# FC_MC_SCH.net
KiCad netlist of a schematic drawn in Altium Designer
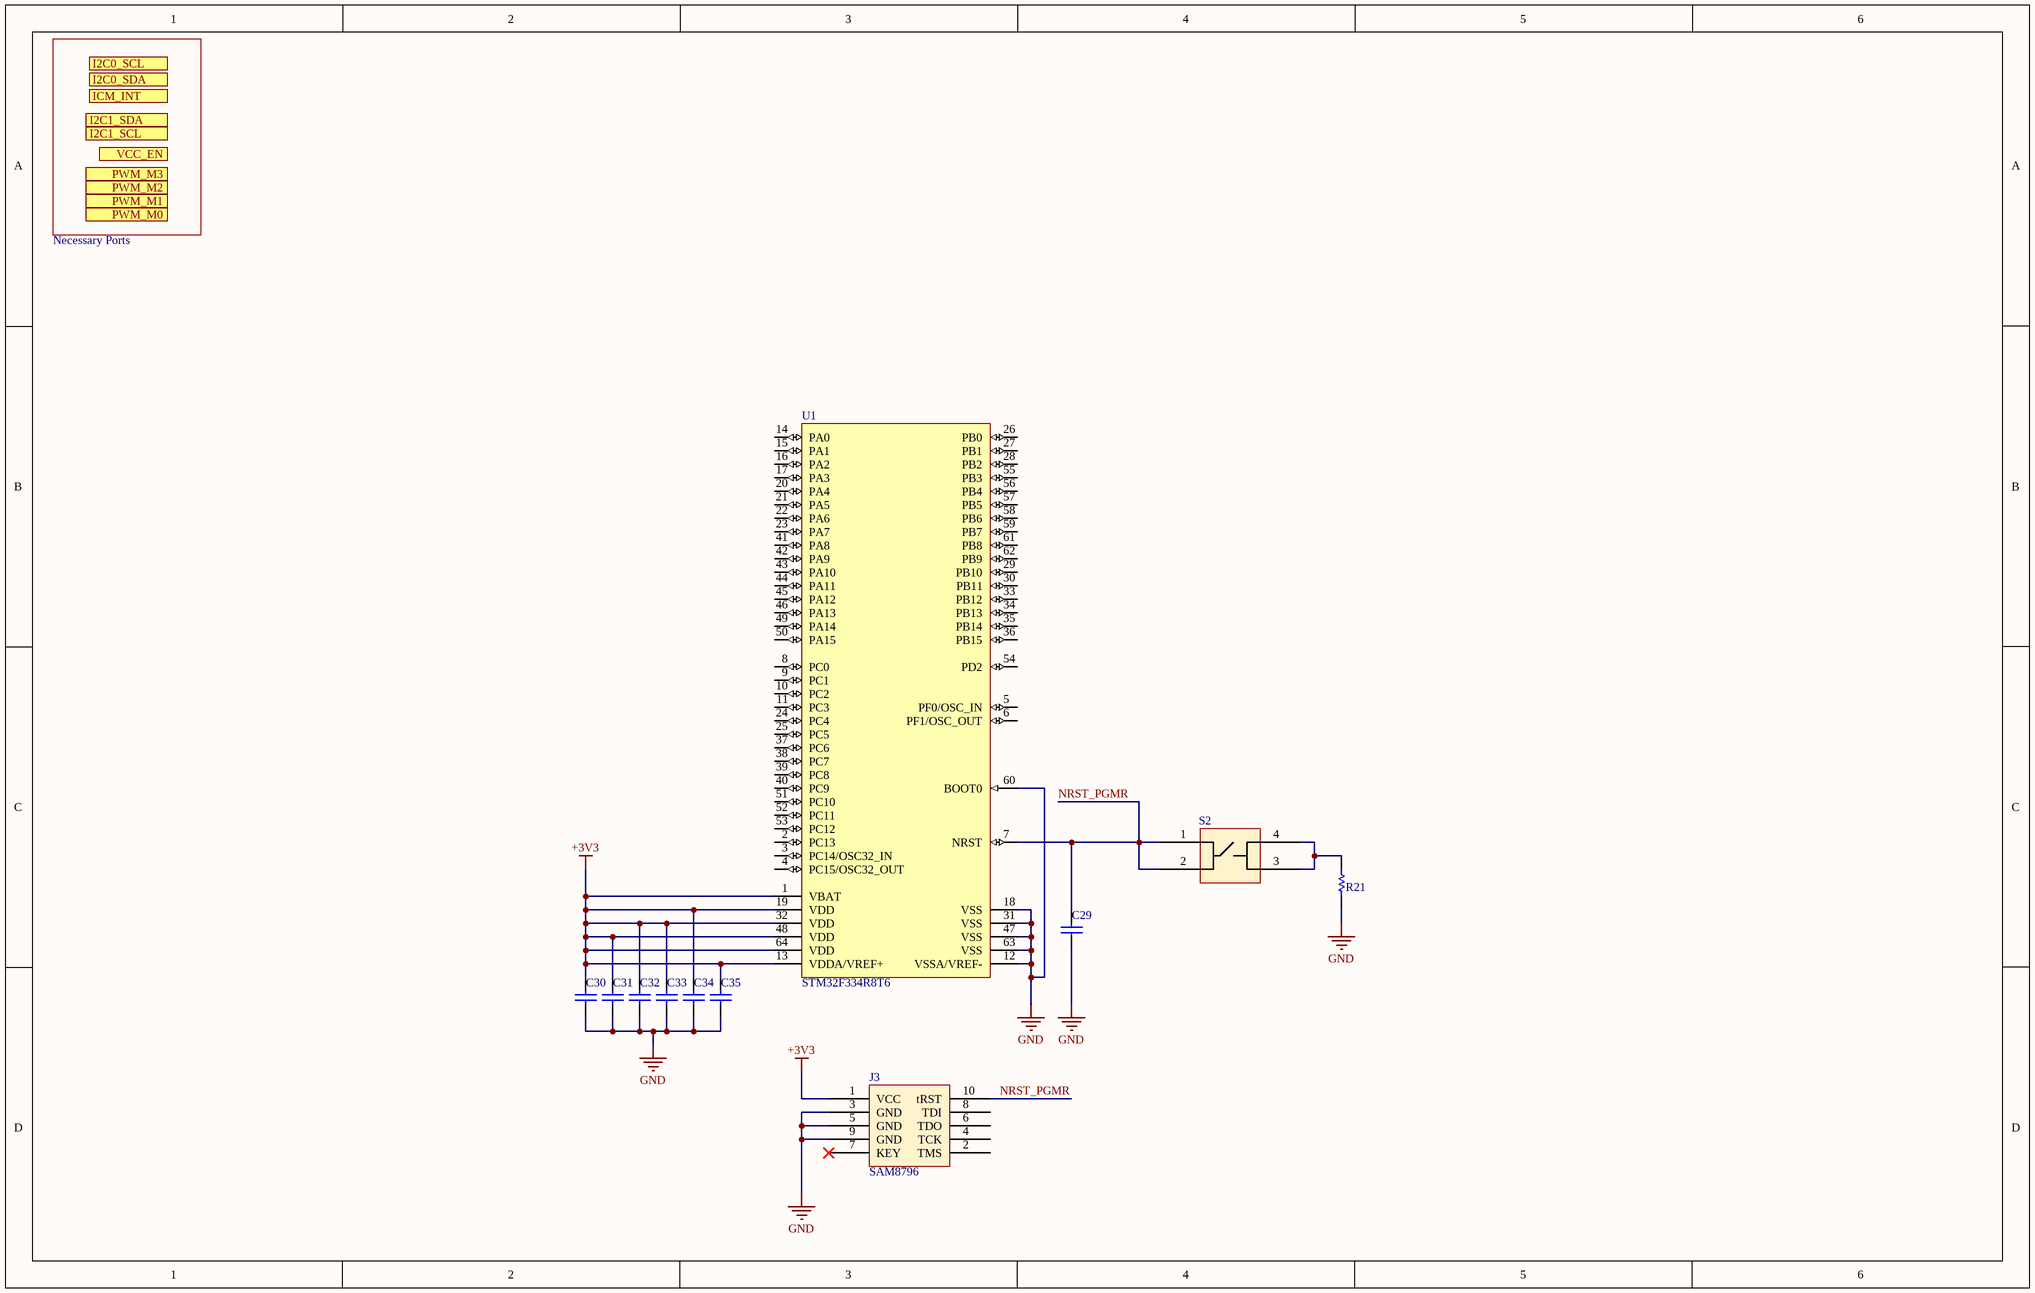
[diagram p0: FC_MC_SCH.SchDoc]

(export (version "E")
  (design (tool "Eeschema 10.0.6"))
  (components
    (comp (ref "C29")
      (value "CAP0402")
      (footprint "CAPC0402(1005)60_L")
      (description "0402 (1005 Metric) Chip Capacitor")
      (libsource (lib "Altium Content Vault") (part "CAP_5"))
    )
    (comp (ref "C30")
      (value "CAP0402")
      (footprint "CAPC0402(1005)60_L")
      (description "0402 (1005 Metric) Chip Capacitor")
      (libsource (lib "Altium Content Vault") (part "CAP_5"))
    )
    (comp (ref "C31")
      (value "CAP0402")
      (footprint "CAPC0402(1005)60_L")
      (description "0402 (1005 Metric) Chip Capacitor")
      (libsource (lib "Altium Content Vault") (part "CAP_5"))
    )
    (comp (ref "C32")
      (value "CAP0402")
      (footprint "CAPC0402(1005)60_L")
      (description "0402 (1005 Metric) Chip Capacitor")
      (libsource (lib "Altium Content Vault") (part "CAP_5"))
    )
    (comp (ref "C33")
      (value "CAP0402")
      (footprint "CAPC0402(1005)60_L")
      (description "0402 (1005 Metric) Chip Capacitor")
      (libsource (lib "Altium Content Vault") (part "CAP_5"))
    )
    (comp (ref "C34")
      (value "CAP0402")
      (footprint "CAPC0402(1005)60_L")
      (description "0402 (1005 Metric) Chip Capacitor")
      (libsource (lib "Altium Content Vault") (part "CAP_5"))
    )
    (comp (ref "C35")
      (value "CAP0402")
      (footprint "CAPC0402(1005)60_L")
      (description "0402 (1005 Metric) Chip Capacitor")
      (libsource (lib "Altium Content Vault") (part "CAP_5"))
    )
    (comp (ref "J3") (value "SAM8796") (libsource (lib "Copter") (part "SAM8796")))
    (comp (ref "R21") (value "RES-2") (footprint "RES 0402") (libsource (lib "Copter") (part "RES")))
    (comp (ref "S2") (value "PTS 647") (libsource (lib "Copter") (part "TactileSW")))
    (comp (ref "U1")
      (value "STM32F334R8T6")
      (footprint "STM-LQFP64_L")
      (libsource (lib "Altium Content Vault") (part "MC-ARM-STM32F334-LQFP64"))
    )
  )
  (nets
    (net (code "1") (name "+3V3") (class "Default")
      (node (ref "C30") (pin "2") (pinfunction "2_2") (pintype "passive"))
      (node (ref "C31") (pin "2") (pinfunction "2_2") (pintype "passive"))
      (node (ref "C32") (pin "2") (pinfunction "2_2") (pintype "passive"))
      (node (ref "C33") (pin "2") (pinfunction "2_2") (pintype "passive"))
      (node (ref "C34") (pin "2") (pinfunction "2_2") (pintype "passive"))
      (node (ref "C35") (pin "2") (pinfunction "2_2") (pintype "passive"))
      (node (ref "J3") (pin "1") (pinfunction "VCC_1") (pintype "passive"))
      (node (ref "U1") (pin "1") (pinfunction "VBAT_1") (pintype "power_in"))
      (node (ref "U1") (pin "13") (pinfunction "VDDA/VREF+_13") (pintype "power_in"))
      (node (ref "U1") (pin "19") (pinfunction "VDD_19") (pintype "power_in"))
      (node (ref "U1") (pin "32") (pinfunction "VDD_32") (pintype "power_in"))
      (node (ref "U1") (pin "48") (pinfunction "VDD_48") (pintype "power_in"))
      (node (ref "U1") (pin "64") (pinfunction "VDD_64") (pintype "power_in"))
    )
    (net (code "7") (name "/NRST_PGMR") (class "Default")
      (node (ref "C29") (pin "2") (pinfunction "2_2") (pintype "passive"))
      (node (ref "J3") (pin "10") (pinfunction "tRST_10") (pintype "passive"))
      (node (ref "S2") (pin "1") (pintype "passive"))
      (node (ref "S2") (pin "2") (pintype "passive"))
      (node (ref "U1") (pin "7") (pinfunction "NRST_7") (pintype "bidirectional"))
    )
    (net (code "13") (name "GND") (class "Default")
      (node (ref "C29") (pin "1") (pinfunction "1_1") (pintype "passive"))
      (node (ref "C30") (pin "1") (pinfunction "1_1") (pintype "passive"))
      (node (ref "C31") (pin "1") (pinfunction "1_1") (pintype "passive"))
      (node (ref "C32") (pin "1") (pinfunction "1_1") (pintype "passive"))
      (node (ref "C33") (pin "1") (pinfunction "1_1") (pintype "passive"))
      (node (ref "C34") (pin "1") (pinfunction "1_1") (pintype "passive"))
      (node (ref "C35") (pin "1") (pinfunction "1_1") (pintype "passive"))
      (node (ref "J3") (pin "3") (pinfunction "GND_3") (pintype "passive"))
      (node (ref "J3") (pin "5") (pinfunction "GND_5") (pintype "passive"))
      (node (ref "J3") (pin "9") (pinfunction "GND_9") (pintype "passive"))
      (node (ref "R21") (pin "2") (pinfunction "2_2") (pintype "passive"))
      (node (ref "U1") (pin "12") (pinfunction "VSSA/VREF-_12") (pintype "power_in"))
      (node (ref "U1") (pin "18") (pinfunction "VSS_18") (pintype "power_in"))
      (node (ref "U1") (pin "31") (pinfunction "VSS_31") (pintype "power_in"))
      (node (ref "U1") (pin "47") (pinfunction "VSS_47") (pintype "power_in"))
      (node (ref "U1") (pin "60") (pinfunction "BOOT0_60") (pintype "input"))
      (node (ref "U1") (pin "63") (pinfunction "VSS_63") (pintype "power_in"))
    )
    (net (code "14") (name "Net-(R21-Pad1)") (class "Default")
      (node (ref "R21") (pin "1") (pinfunction "1_1") (pintype "passive"))
      (node (ref "S2") (pin "3") (pintype "passive"))
      (node (ref "S2") (pin "4") (pintype "passive"))
    )
    (net (code "15") (name "unconnected-(J3-KEY-Pad7)") (class "Default")
      (node (ref "J3") (pin "7") (pinfunction "KEY_7") (pintype "passive+no_connect"))
    )
    (net (code "16") (name "unconnected-(J3-TCK-Pad4)") (class "Default")
      (node (ref "J3") (pin "4") (pinfunction "TCK_4") (pintype "passive"))
    )
    (net (code "17") (name "unconnected-(J3-TDI-Pad8)") (class "Default")
      (node (ref "J3") (pin "8") (pinfunction "TDI_8") (pintype "passive"))
    )
    (net (code "18") (name "unconnected-(J3-TDO-Pad6)") (class "Default")
      (node (ref "J3") (pin "6") (pinfunction "TDO_6") (pintype "passive"))
    )
    (net (code "19") (name "unconnected-(J3-TMS-Pad2)") (class "Default")
      (node (ref "J3") (pin "2") (pinfunction "TMS_2") (pintype "passive"))
    )
    (net (code "20") (name "unconnected-(U1-PA0-Pad14)") (class "Default")
      (node (ref "U1") (pin "14") (pinfunction "PA0_14") (pintype "bidirectional"))
    )
    (net (code "21") (name "unconnected-(U1-PA1-Pad15)") (class "Default")
      (node (ref "U1") (pin "15") (pinfunction "PA1_15") (pintype "bidirectional"))
    )
    (net (code "22") (name "unconnected-(U1-PA2-Pad16)") (class "Default")
      (node (ref "U1") (pin "16") (pinfunction "PA2_16") (pintype "bidirectional"))
    )
    (net (code "23") (name "unconnected-(U1-PA3-Pad17)") (class "Default")
      (node (ref "U1") (pin "17") (pinfunction "PA3_17") (pintype "bidirectional"))
    )
    (net (code "24") (name "unconnected-(U1-PA4-Pad20)") (class "Default")
      (node (ref "U1") (pin "20") (pinfunction "PA4_20") (pintype "bidirectional"))
    )
    (net (code "25") (name "unconnected-(U1-PA5-Pad21)") (class "Default")
      (node (ref "U1") (pin "21") (pinfunction "PA5_21") (pintype "bidirectional"))
    )
    (net (code "26") (name "unconnected-(U1-PA6-Pad22)") (class "Default")
      (node (ref "U1") (pin "22") (pinfunction "PA6_22") (pintype "bidirectional"))
    )
    (net (code "27") (name "unconnected-(U1-PA7-Pad23)") (class "Default")
      (node (ref "U1") (pin "23") (pinfunction "PA7_23") (pintype "bidirectional"))
    )
    (net (code "28") (name "unconnected-(U1-PA8-Pad41)") (class "Default")
      (node (ref "U1") (pin "41") (pinfunction "PA8_41") (pintype "bidirectional"))
    )
    (net (code "29") (name "unconnected-(U1-PA9-Pad42)") (class "Default")
      (node (ref "U1") (pin "42") (pinfunction "PA9_42") (pintype "bidirectional"))
    )
    (net (code "30") (name "unconnected-(U1-PA10-Pad43)") (class "Default")
      (node (ref "U1") (pin "43") (pinfunction "PA10_43") (pintype "bidirectional"))
    )
    (net (code "31") (name "unconnected-(U1-PA11-Pad44)") (class "Default")
      (node (ref "U1") (pin "44") (pinfunction "PA11_44") (pintype "bidirectional"))
    )
    (net (code "32") (name "unconnected-(U1-PA12-Pad45)") (class "Default")
      (node (ref "U1") (pin "45") (pinfunction "PA12_45") (pintype "bidirectional"))
    )
    (net (code "33") (name "unconnected-(U1-PA13-Pad46)") (class "Default")
      (node (ref "U1") (pin "46") (pinfunction "PA13_46") (pintype "bidirectional"))
    )
    (net (code "34") (name "unconnected-(U1-PA14-Pad49)") (class "Default")
      (node (ref "U1") (pin "49") (pinfunction "PA14_49") (pintype "bidirectional"))
    )
    (net (code "35") (name "unconnected-(U1-PA15-Pad50)") (class "Default")
      (node (ref "U1") (pin "50") (pinfunction "PA15_50") (pintype "bidirectional"))
    )
    (net (code "36") (name "unconnected-(U1-PB0-Pad26)") (class "Default")
      (node (ref "U1") (pin "26") (pinfunction "PB0_26") (pintype "bidirectional"))
    )
    (net (code "37") (name "unconnected-(U1-PB1-Pad27)") (class "Default")
      (node (ref "U1") (pin "27") (pinfunction "PB1_27") (pintype "bidirectional"))
    )
    (net (code "38") (name "unconnected-(U1-PB2-Pad28)") (class "Default")
      (node (ref "U1") (pin "28") (pinfunction "PB2_28") (pintype "bidirectional"))
    )
    (net (code "39") (name "unconnected-(U1-PB3-Pad55)") (class "Default")
      (node (ref "U1") (pin "55") (pinfunction "PB3_55") (pintype "bidirectional"))
    )
    (net (code "40") (name "unconnected-(U1-PB4-Pad56)") (class "Default")
      (node (ref "U1") (pin "56") (pinfunction "PB4_56") (pintype "bidirectional"))
    )
    (net (code "41") (name "unconnected-(U1-PB5-Pad57)") (class "Default")
      (node (ref "U1") (pin "57") (pinfunction "PB5_57") (pintype "bidirectional"))
    )
    (net (code "42") (name "unconnected-(U1-PB6-Pad58)") (class "Default")
      (node (ref "U1") (pin "58") (pinfunction "PB6_58") (pintype "bidirectional"))
    )
    (net (code "43") (name "unconnected-(U1-PB7-Pad59)") (class "Default")
      (node (ref "U1") (pin "59") (pinfunction "PB7_59") (pintype "bidirectional"))
    )
    (net (code "44") (name "unconnected-(U1-PB8-Pad61)") (class "Default")
      (node (ref "U1") (pin "61") (pinfunction "PB8_61") (pintype "bidirectional"))
    )
    (net (code "45") (name "unconnected-(U1-PB9-Pad62)") (class "Default")
      (node (ref "U1") (pin "62") (pinfunction "PB9_62") (pintype "bidirectional"))
    )
    (net (code "46") (name "unconnected-(U1-PB10-Pad29)") (class "Default")
      (node (ref "U1") (pin "29") (pinfunction "PB10_29") (pintype "bidirectional"))
    )
    (net (code "47") (name "unconnected-(U1-PB11-Pad30)") (class "Default")
      (node (ref "U1") (pin "30") (pinfunction "PB11_30") (pintype "bidirectional"))
    )
    (net (code "48") (name "unconnected-(U1-PB12-Pad33)") (class "Default")
      (node (ref "U1") (pin "33") (pinfunction "PB12_33") (pintype "bidirectional"))
    )
    (net (code "49") (name "unconnected-(U1-PB13-Pad34)") (class "Default")
      (node (ref "U1") (pin "34") (pinfunction "PB13_34") (pintype "bidirectional"))
    )
    (net (code "50") (name "unconnected-(U1-PB14-Pad35)") (class "Default")
      (node (ref "U1") (pin "35") (pinfunction "PB14_35") (pintype "bidirectional"))
    )
    (net (code "51") (name "unconnected-(U1-PB15-Pad36)") (class "Default")
      (node (ref "U1") (pin "36") (pinfunction "PB15_36") (pintype "bidirectional"))
    )
    (net (code "52") (name "unconnected-(U1-PC0-Pad8)") (class "Default")
      (node (ref "U1") (pin "8") (pinfunction "PC0_8") (pintype "bidirectional"))
    )
    (net (code "53") (name "unconnected-(U1-PC1-Pad9)") (class "Default")
      (node (ref "U1") (pin "9") (pinfunction "PC1_9") (pintype "bidirectional"))
    )
    (net (code "54") (name "unconnected-(U1-PC2-Pad10)") (class "Default")
      (node (ref "U1") (pin "10") (pinfunction "PC2_10") (pintype "bidirectional"))
    )
    (net (code "55") (name "unconnected-(U1-PC3-Pad11)") (class "Default")
      (node (ref "U1") (pin "11") (pinfunction "PC3_11") (pintype "bidirectional"))
    )
    (net (code "56") (name "unconnected-(U1-PC4-Pad24)") (class "Default")
      (node (ref "U1") (pin "24") (pinfunction "PC4_24") (pintype "bidirectional"))
    )
    (net (code "57") (name "unconnected-(U1-PC5-Pad25)") (class "Default")
      (node (ref "U1") (pin "25") (pinfunction "PC5_25") (pintype "bidirectional"))
    )
    (net (code "58") (name "unconnected-(U1-PC6-Pad37)") (class "Default")
      (node (ref "U1") (pin "37") (pinfunction "PC6_37") (pintype "bidirectional"))
    )
    (net (code "59") (name "unconnected-(U1-PC7-Pad38)") (class "Default")
      (node (ref "U1") (pin "38") (pinfunction "PC7_38") (pintype "bidirectional"))
    )
    (net (code "60") (name "unconnected-(U1-PC8-Pad39)") (class "Default")
      (node (ref "U1") (pin "39") (pinfunction "PC8_39") (pintype "bidirectional"))
    )
    (net (code "61") (name "unconnected-(U1-PC9-Pad40)") (class "Default")
      (node (ref "U1") (pin "40") (pinfunction "PC9_40") (pintype "bidirectional"))
    )
    (net (code "62") (name "unconnected-(U1-PC10-Pad51)") (class "Default")
      (node (ref "U1") (pin "51") (pinfunction "PC10_51") (pintype "bidirectional"))
    )
    (net (code "63") (name "unconnected-(U1-PC11-Pad52)") (class "Default")
      (node (ref "U1") (pin "52") (pinfunction "PC11_52") (pintype "bidirectional"))
    )
    (net (code "64") (name "unconnected-(U1-PC12-Pad53)") (class "Default")
      (node (ref "U1") (pin "53") (pinfunction "PC12_53") (pintype "bidirectional"))
    )
    (net (code "65") (name "unconnected-(U1-PC13-Pad2)") (class "Default")
      (node (ref "U1") (pin "2") (pinfunction "PC13_2") (pintype "bidirectional"))
    )
    (net (code "66") (name "unconnected-(U1-PC14{slash}OSC32_IN-Pad3)") (class "Default")
      (node (ref "U1") (pin "3") (pinfunction "PC14/OSC32_IN_3") (pintype "bidirectional"))
    )
    (net (code "67") (name "unconnected-(U1-PC15{slash}OSC32_OUT-Pad4)") (class "Default")
      (node (ref "U1") (pin "4") (pinfunction "PC15/OSC32_OUT_4") (pintype "bidirectional"))
    )
    (net (code "68") (name "unconnected-(U1-PD2-Pad54)") (class "Default")
      (node (ref "U1") (pin "54") (pinfunction "PD2_54") (pintype "bidirectional"))
    )
    (net (code "69") (name "unconnected-(U1-PF0{slash}OSC_IN-Pad5)") (class "Default")
      (node (ref "U1") (pin "5") (pinfunction "PF0/OSC_IN_5") (pintype "bidirectional"))
    )
    (net (code "70") (name "unconnected-(U1-PF1{slash}OSC_OUT-Pad6)") (class "Default")
      (node (ref "U1") (pin "6") (pinfunction "PF1/OSC_OUT_6") (pintype "bidirectional"))
    )
  )
)
